# electrical_diagram.net
KiCad netlist of a schematic drawn in EAGLE
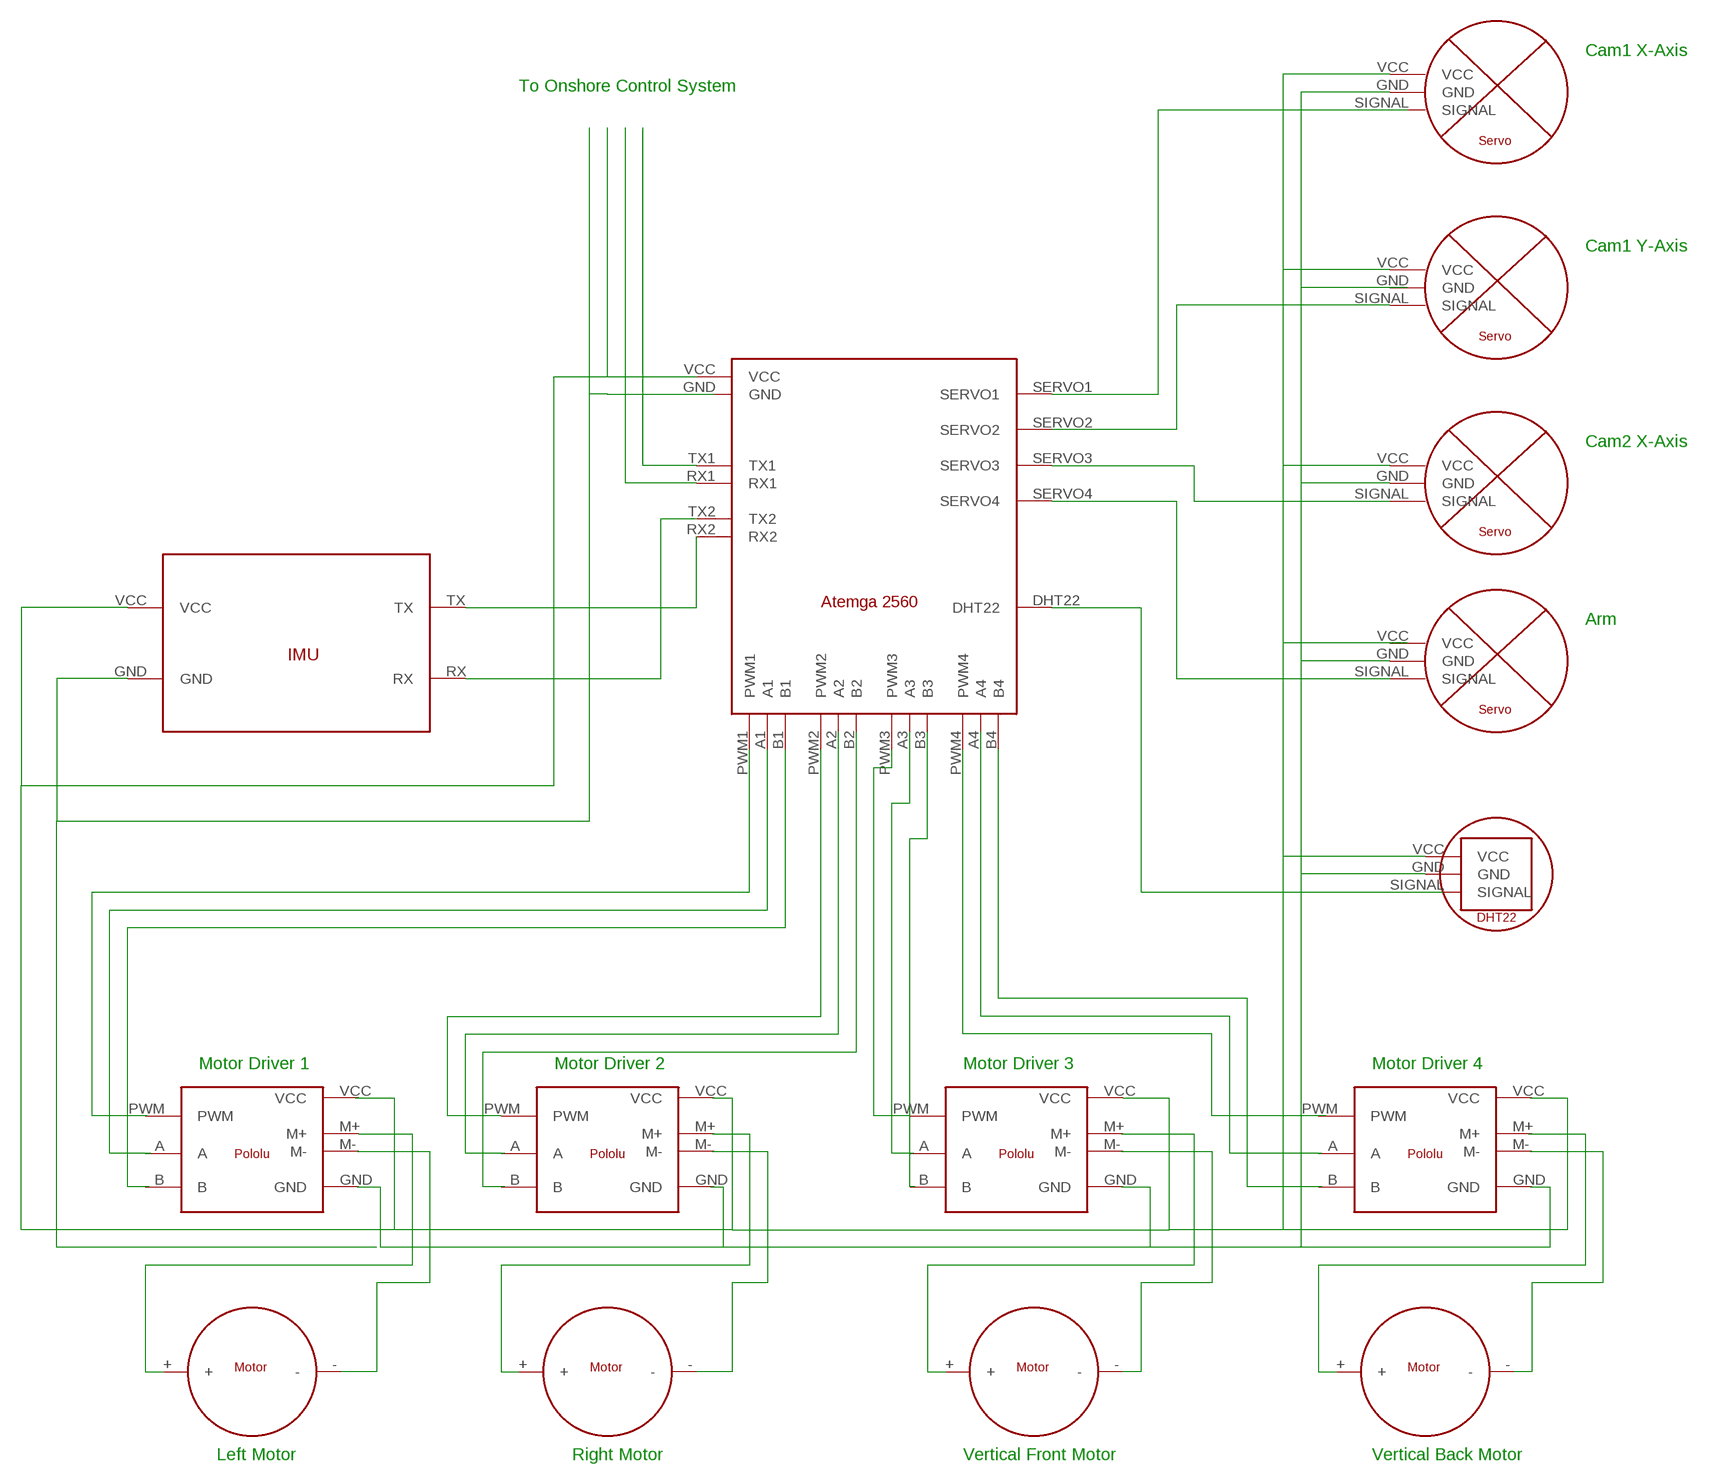
[diagram p0: schematic, sheet 1]

(export (version "E")
  (design (tool "Eeschema 10.0.6"))
  (components
    (comp (ref "U$2")
      (value "POLOLU_MOTOR")
      (footprint "eagle-import:POLOLU_MOTOR")
      (libsource (lib "eagle-import") (part "POLOLU_MOTOR"))
    )
    (comp (ref "U$3")
      (value "POLOLU_MOTOR")
      (footprint "eagle-import:POLOLU_MOTOR")
      (libsource (lib "eagle-import") (part "POLOLU_MOTOR"))
    )
    (comp (ref "U$4")
      (value "POLOLU_MOTOR")
      (footprint "eagle-import:POLOLU_MOTOR")
      (libsource (lib "eagle-import") (part "POLOLU_MOTOR"))
    )
    (comp (ref "U$5")
      (value "POLOLU_MOTOR")
      (footprint "eagle-import:POLOLU_MOTOR")
      (libsource (lib "eagle-import") (part "POLOLU_MOTOR"))
    )
    (comp (ref "U$6")
      (value "MOTOR")
      (footprint "eagle-import:MOTOR")
      (libsource (lib "eagle-import") (part "MOTOR"))
    )
    (comp (ref "U$7")
      (value "MOTOR")
      (footprint "eagle-import:MOTOR")
      (libsource (lib "eagle-import") (part "MOTOR"))
    )
    (comp (ref "U$8")
      (value "MOTOR")
      (footprint "eagle-import:MOTOR")
      (libsource (lib "eagle-import") (part "MOTOR"))
    )
    (comp (ref "U$9")
      (value "MOTOR")
      (footprint "eagle-import:MOTOR")
      (libsource (lib "eagle-import") (part "MOTOR"))
    )
    (comp (ref "U$10")
      (value "SERVO")
      (footprint "eagle-import:SERVO")
      (libsource (lib "eagle-import") (part "SERVO"))
    )
    (comp (ref "U$11")
      (value "SERVO")
      (footprint "eagle-import:SERVO")
      (libsource (lib "eagle-import") (part "SERVO"))
    )
    (comp (ref "U$12")
      (value "SERVO")
      (footprint "eagle-import:SERVO")
      (libsource (lib "eagle-import") (part "SERVO"))
    )
    (comp (ref "U$13")
      (value "SERVO")
      (footprint "eagle-import:SERVO")
      (libsource (lib "eagle-import") (part "SERVO"))
    )
    (comp (ref "U$14")
      (value "ROV_MCU")
      (footprint "eagle-import:ROV_MCU")
      (libsource (lib "eagle-import") (part "ROV_MCU"))
    )
    (comp (ref "U$15")
      (value "IMU")
      (footprint "eagle-import:IMU")
      (libsource (lib "eagle-import") (part "IMU"))
    )
    (comp (ref "U$16")
      (value "DHT22")
      (footprint "eagle-import:DHT22")
      (libsource (lib "eagle-import") (part "DHT22"))
    )
  )
  (nets
    (net (code "1") (name "Net-(U$10-PadGND)") (class "Default")
      (node (ref "U$10") (pin "GND") (pinfunction "GND_GND") (pintype "bidirectional"))
      (node (ref "U$12") (pin "GND") (pinfunction "GND_GND") (pintype "bidirectional"))
      (node (ref "U$13") (pin "GND") (pinfunction "GND_GND") (pintype "bidirectional"))
      (node (ref "U$16") (pin "GND") (pinfunction "GND_GND") (pintype "bidirectional"))
    )
    (net (code "2") (name "Net-(U$10-PadVCC)") (class "Default")
      (node (ref "U$10") (pin "VCC") (pinfunction "VCC_VCC") (pintype "bidirectional"))
      (node (ref "U$11") (pin "VCC") (pinfunction "VCC_VCC") (pintype "bidirectional"))
      (node (ref "U$12") (pin "VCC") (pinfunction "VCC_VCC") (pintype "bidirectional"))
      (node (ref "U$14") (pin "VCC") (pinfunction "VCC_VCC") (pintype "bidirectional"))
      (node (ref "U$15") (pin "VCC") (pinfunction "VCC_VCC") (pintype "bidirectional"))
      (node (ref "U$16") (pin "VCC") (pinfunction "VCC_VCC") (pintype "bidirectional"))
      (node (ref "U$4") (pin "VCC") (pinfunction "VCC_VCC") (pintype "bidirectional"))
    )
    (net (code "3") (name "Net-(U$11-PadSIGNAL)") (class "Default")
      (node (ref "U$11") (pin "SIGNAL") (pinfunction "SIGNAL_SIGNAL") (pintype "bidirectional"))
      (node (ref "U$14") (pin "SERVO2") (pinfunction "SERVO2_SERVO2") (pintype "bidirectional"))
    )
    (net (code "4") (name "Net-(U$12-PadSIGNAL)") (class "Default")
      (node (ref "U$12") (pin "SIGNAL") (pinfunction "SIGNAL_SIGNAL") (pintype "bidirectional"))
      (node (ref "U$14") (pin "SERVO3") (pinfunction "SERVO3_SERVO3") (pintype "bidirectional"))
    )
    (net (code "5") (name "Net-(U$13-PadSIGNAL)") (class "Default")
      (node (ref "U$13") (pin "SIGNAL") (pinfunction "SIGNAL_SIGNAL") (pintype "bidirectional"))
      (node (ref "U$14") (pin "SERVO4") (pinfunction "SERVO4_SERVO4") (pintype "bidirectional"))
    )
    (net (code "6") (name "Net-(U$14-PadPWM2)") (class "Default")
      (node (ref "U$14") (pin "PWM2") (pinfunction "PWM2_PWM2") (pintype "bidirectional"))
      (node (ref "U$3") (pin "PWM") (pinfunction "PWM_PWM") (pintype "bidirectional"))
    )
    (net (code "7") (name "Net-(U$14-PadPWM3)") (class "Default")
      (node (ref "U$14") (pin "PWM3") (pinfunction "PWM3_PWM3") (pintype "bidirectional"))
      (node (ref "U$4") (pin "PWM") (pinfunction "PWM_PWM") (pintype "bidirectional"))
    )
    (net (code "8") (name "Net-(U$14-PadRX2)") (class "Default")
      (node (ref "U$14") (pin "RX2") (pinfunction "RX2_RX2") (pintype "bidirectional"))
      (node (ref "U$15") (pin "TX") (pinfunction "TX_TX") (pintype "bidirectional"))
    )
    (net (code "9") (name "Net-(U$14-PadTX2)") (class "Default")
      (node (ref "U$14") (pin "TX2") (pinfunction "TX2_TX2") (pintype "bidirectional"))
      (node (ref "U$15") (pin "RX") (pinfunction "RX_RX") (pintype "bidirectional"))
    )
    (net (code "10") (name "unconnected-(U$2-PadA)") (class "Default")
      (node (ref "U$2") (pin "A") (pinfunction "A_A") (pintype "bidirectional"))
    )
    (net (code "11") (name "unconnected-(U$2-PadB)") (class "Default")
      (node (ref "U$2") (pin "B") (pinfunction "B_B") (pintype "bidirectional"))
    )
    (net (code "12") (name "unconnected-(U$2-PadGND)") (class "Default")
      (node (ref "U$2") (pin "GND") (pinfunction "GND_GND") (pintype "bidirectional"))
    )
    (net (code "13") (name "unconnected-(U$2-PadM+)") (class "Default")
      (node (ref "U$2") (pin "M+") (pinfunction "M+_M+") (pintype "bidirectional"))
    )
    (net (code "14") (name "unconnected-(U$2-PadM-)") (class "Default")
      (node (ref "U$2") (pin "M-") (pinfunction "M-_M-") (pintype "bidirectional"))
    )
    (net (code "15") (name "unconnected-(U$2-PadPWM)") (class "Default")
      (node (ref "U$2") (pin "PWM") (pinfunction "PWM_PWM") (pintype "bidirectional"))
    )
    (net (code "16") (name "unconnected-(U$2-PadVCC)") (class "Default")
      (node (ref "U$2") (pin "VCC") (pinfunction "VCC_VCC") (pintype "bidirectional"))
    )
    (net (code "17") (name "unconnected-(U$3-PadA)") (class "Default")
      (node (ref "U$3") (pin "A") (pinfunction "A_A") (pintype "bidirectional"))
    )
    (net (code "18") (name "unconnected-(U$3-PadB)") (class "Default")
      (node (ref "U$3") (pin "B") (pinfunction "B_B") (pintype "bidirectional"))
    )
    (net (code "19") (name "unconnected-(U$3-PadGND)") (class "Default")
      (node (ref "U$3") (pin "GND") (pinfunction "GND_GND") (pintype "bidirectional"))
    )
    (net (code "20") (name "unconnected-(U$3-PadM+)") (class "Default")
      (node (ref "U$3") (pin "M+") (pinfunction "M+_M+") (pintype "bidirectional"))
    )
    (net (code "21") (name "unconnected-(U$3-PadM-)") (class "Default")
      (node (ref "U$3") (pin "M-") (pinfunction "M-_M-") (pintype "bidirectional"))
    )
    (net (code "22") (name "unconnected-(U$3-PadVCC)") (class "Default")
      (node (ref "U$3") (pin "VCC") (pinfunction "VCC_VCC") (pintype "bidirectional"))
    )
    (net (code "23") (name "unconnected-(U$4-PadA)") (class "Default")
      (node (ref "U$4") (pin "A") (pinfunction "A_A") (pintype "bidirectional"))
    )
    (net (code "24") (name "unconnected-(U$4-PadB)") (class "Default")
      (node (ref "U$4") (pin "B") (pinfunction "B_B") (pintype "bidirectional"))
    )
    (net (code "25") (name "unconnected-(U$4-PadGND)") (class "Default")
      (node (ref "U$4") (pin "GND") (pinfunction "GND_GND") (pintype "bidirectional"))
    )
    (net (code "26") (name "unconnected-(U$4-PadM+)") (class "Default")
      (node (ref "U$4") (pin "M+") (pinfunction "M+_M+") (pintype "bidirectional"))
    )
    (net (code "27") (name "unconnected-(U$4-PadM-)") (class "Default")
      (node (ref "U$4") (pin "M-") (pinfunction "M-_M-") (pintype "bidirectional"))
    )
    (net (code "28") (name "unconnected-(U$5-PadA)") (class "Default")
      (node (ref "U$5") (pin "A") (pinfunction "A_A") (pintype "bidirectional"))
    )
    (net (code "29") (name "unconnected-(U$5-PadB)") (class "Default")
      (node (ref "U$5") (pin "B") (pinfunction "B_B") (pintype "bidirectional"))
    )
    (net (code "30") (name "unconnected-(U$5-PadGND)") (class "Default")
      (node (ref "U$5") (pin "GND") (pinfunction "GND_GND") (pintype "bidirectional"))
    )
    (net (code "31") (name "unconnected-(U$5-PadM+)") (class "Default")
      (node (ref "U$5") (pin "M+") (pinfunction "M+_M+") (pintype "bidirectional"))
    )
    (net (code "32") (name "unconnected-(U$5-PadM-)") (class "Default")
      (node (ref "U$5") (pin "M-") (pinfunction "M-_M-") (pintype "bidirectional"))
    )
    (net (code "33") (name "unconnected-(U$5-PadPWM)") (class "Default")
      (node (ref "U$5") (pin "PWM") (pinfunction "PWM_PWM") (pintype "bidirectional"))
    )
    (net (code "34") (name "unconnected-(U$5-PadVCC)") (class "Default")
      (node (ref "U$5") (pin "VCC") (pinfunction "VCC_VCC") (pintype "bidirectional"))
    )
    (net (code "35") (name "unconnected-(U$6-Pad+)") (class "Default")
      (node (ref "U$6") (pin "+") (pinfunction "+_+") (pintype "bidirectional"))
    )
    (net (code "36") (name "unconnected-(U$6-Pad-)") (class "Default")
      (node (ref "U$6") (pin "-") (pinfunction "-_-") (pintype "bidirectional"))
    )
    (net (code "37") (name "unconnected-(U$7-Pad+)") (class "Default")
      (node (ref "U$7") (pin "+") (pinfunction "+_+") (pintype "bidirectional"))
    )
    (net (code "38") (name "unconnected-(U$7-Pad-)") (class "Default")
      (node (ref "U$7") (pin "-") (pinfunction "-_-") (pintype "bidirectional"))
    )
    (net (code "39") (name "unconnected-(U$8-Pad+)") (class "Default")
      (node (ref "U$8") (pin "+") (pinfunction "+_+") (pintype "bidirectional"))
    )
    (net (code "40") (name "unconnected-(U$8-Pad-)") (class "Default")
      (node (ref "U$8") (pin "-") (pinfunction "-_-") (pintype "bidirectional"))
    )
    (net (code "41") (name "unconnected-(U$9-Pad+)") (class "Default")
      (node (ref "U$9") (pin "+") (pinfunction "+_+") (pintype "bidirectional"))
    )
    (net (code "42") (name "unconnected-(U$9-Pad-)") (class "Default")
      (node (ref "U$9") (pin "-") (pinfunction "-_-") (pintype "bidirectional"))
    )
    (net (code "43") (name "unconnected-(U$10-PadSIGNAL)") (class "Default")
      (node (ref "U$10") (pin "SIGNAL") (pinfunction "SIGNAL_SIGNAL") (pintype "bidirectional"))
    )
    (net (code "44") (name "unconnected-(U$11-PadGND)") (class "Default")
      (node (ref "U$11") (pin "GND") (pinfunction "GND_GND") (pintype "bidirectional"))
    )
    (net (code "45") (name "unconnected-(U$13-PadVCC)") (class "Default")
      (node (ref "U$13") (pin "VCC") (pinfunction "VCC_VCC") (pintype "bidirectional"))
    )
    (net (code "46") (name "unconnected-(U$14-PadA1)") (class "Default")
      (node (ref "U$14") (pin "A1") (pinfunction "A1_A1") (pintype "bidirectional"))
    )
    (net (code "47") (name "unconnected-(U$14-PadA2)") (class "Default")
      (node (ref "U$14") (pin "A2") (pinfunction "A2_A2") (pintype "bidirectional"))
    )
    (net (code "48") (name "unconnected-(U$14-PadA3)") (class "Default")
      (node (ref "U$14") (pin "A3") (pinfunction "A3_A3") (pintype "bidirectional"))
    )
    (net (code "49") (name "unconnected-(U$14-PadA4)") (class "Default")
      (node (ref "U$14") (pin "A4") (pinfunction "A4_A4") (pintype "bidirectional"))
    )
    (net (code "50") (name "unconnected-(U$14-PadB1)") (class "Default")
      (node (ref "U$14") (pin "B1") (pinfunction "B1_B1") (pintype "bidirectional"))
    )
    (net (code "51") (name "unconnected-(U$14-PadB2)") (class "Default")
      (node (ref "U$14") (pin "B2") (pinfunction "B2_B2") (pintype "bidirectional"))
    )
    (net (code "52") (name "unconnected-(U$14-PadB3)") (class "Default")
      (node (ref "U$14") (pin "B3") (pinfunction "B3_B3") (pintype "bidirectional"))
    )
    (net (code "53") (name "unconnected-(U$14-PadB4)") (class "Default")
      (node (ref "U$14") (pin "B4") (pinfunction "B4_B4") (pintype "bidirectional"))
    )
    (net (code "54") (name "unconnected-(U$14-PadDHT22)") (class "Default")
      (node (ref "U$14") (pin "DHT22") (pinfunction "DHT22_DHT22") (pintype "bidirectional"))
    )
    (net (code "55") (name "unconnected-(U$14-PadGND)") (class "Default")
      (node (ref "U$14") (pin "GND") (pinfunction "GND_GND") (pintype "bidirectional"))
    )
    (net (code "56") (name "unconnected-(U$14-PadPWM1)") (class "Default")
      (node (ref "U$14") (pin "PWM1") (pinfunction "PWM1_PWM1") (pintype "bidirectional"))
    )
    (net (code "57") (name "unconnected-(U$14-PadPWM4)") (class "Default")
      (node (ref "U$14") (pin "PWM4") (pinfunction "PWM4_PWM4") (pintype "bidirectional"))
    )
    (net (code "58") (name "unconnected-(U$14-PadRX1)") (class "Default")
      (node (ref "U$14") (pin "RX1") (pinfunction "RX1_RX1") (pintype "bidirectional"))
    )
    (net (code "59") (name "unconnected-(U$14-PadSERVO1)") (class "Default")
      (node (ref "U$14") (pin "SERVO1") (pinfunction "SERVO1_SERVO1") (pintype "bidirectional"))
    )
    (net (code "60") (name "unconnected-(U$14-PadTX1)") (class "Default")
      (node (ref "U$14") (pin "TX1") (pinfunction "TX1_TX1") (pintype "bidirectional"))
    )
    (net (code "61") (name "unconnected-(U$15-PadGND)") (class "Default")
      (node (ref "U$15") (pin "GND") (pinfunction "GND_GND") (pintype "bidirectional"))
    )
    (net (code "62") (name "unconnected-(U$16-PadSIGNAL)") (class "Default")
      (node (ref "U$16") (pin "SIGNAL") (pinfunction "SIGNAL_SIGNAL") (pintype "bidirectional"))
    )
  )
)
